# Sheet_1_2024-04-10.net
KiCad netlist of a schematic drawn in Altium Designer
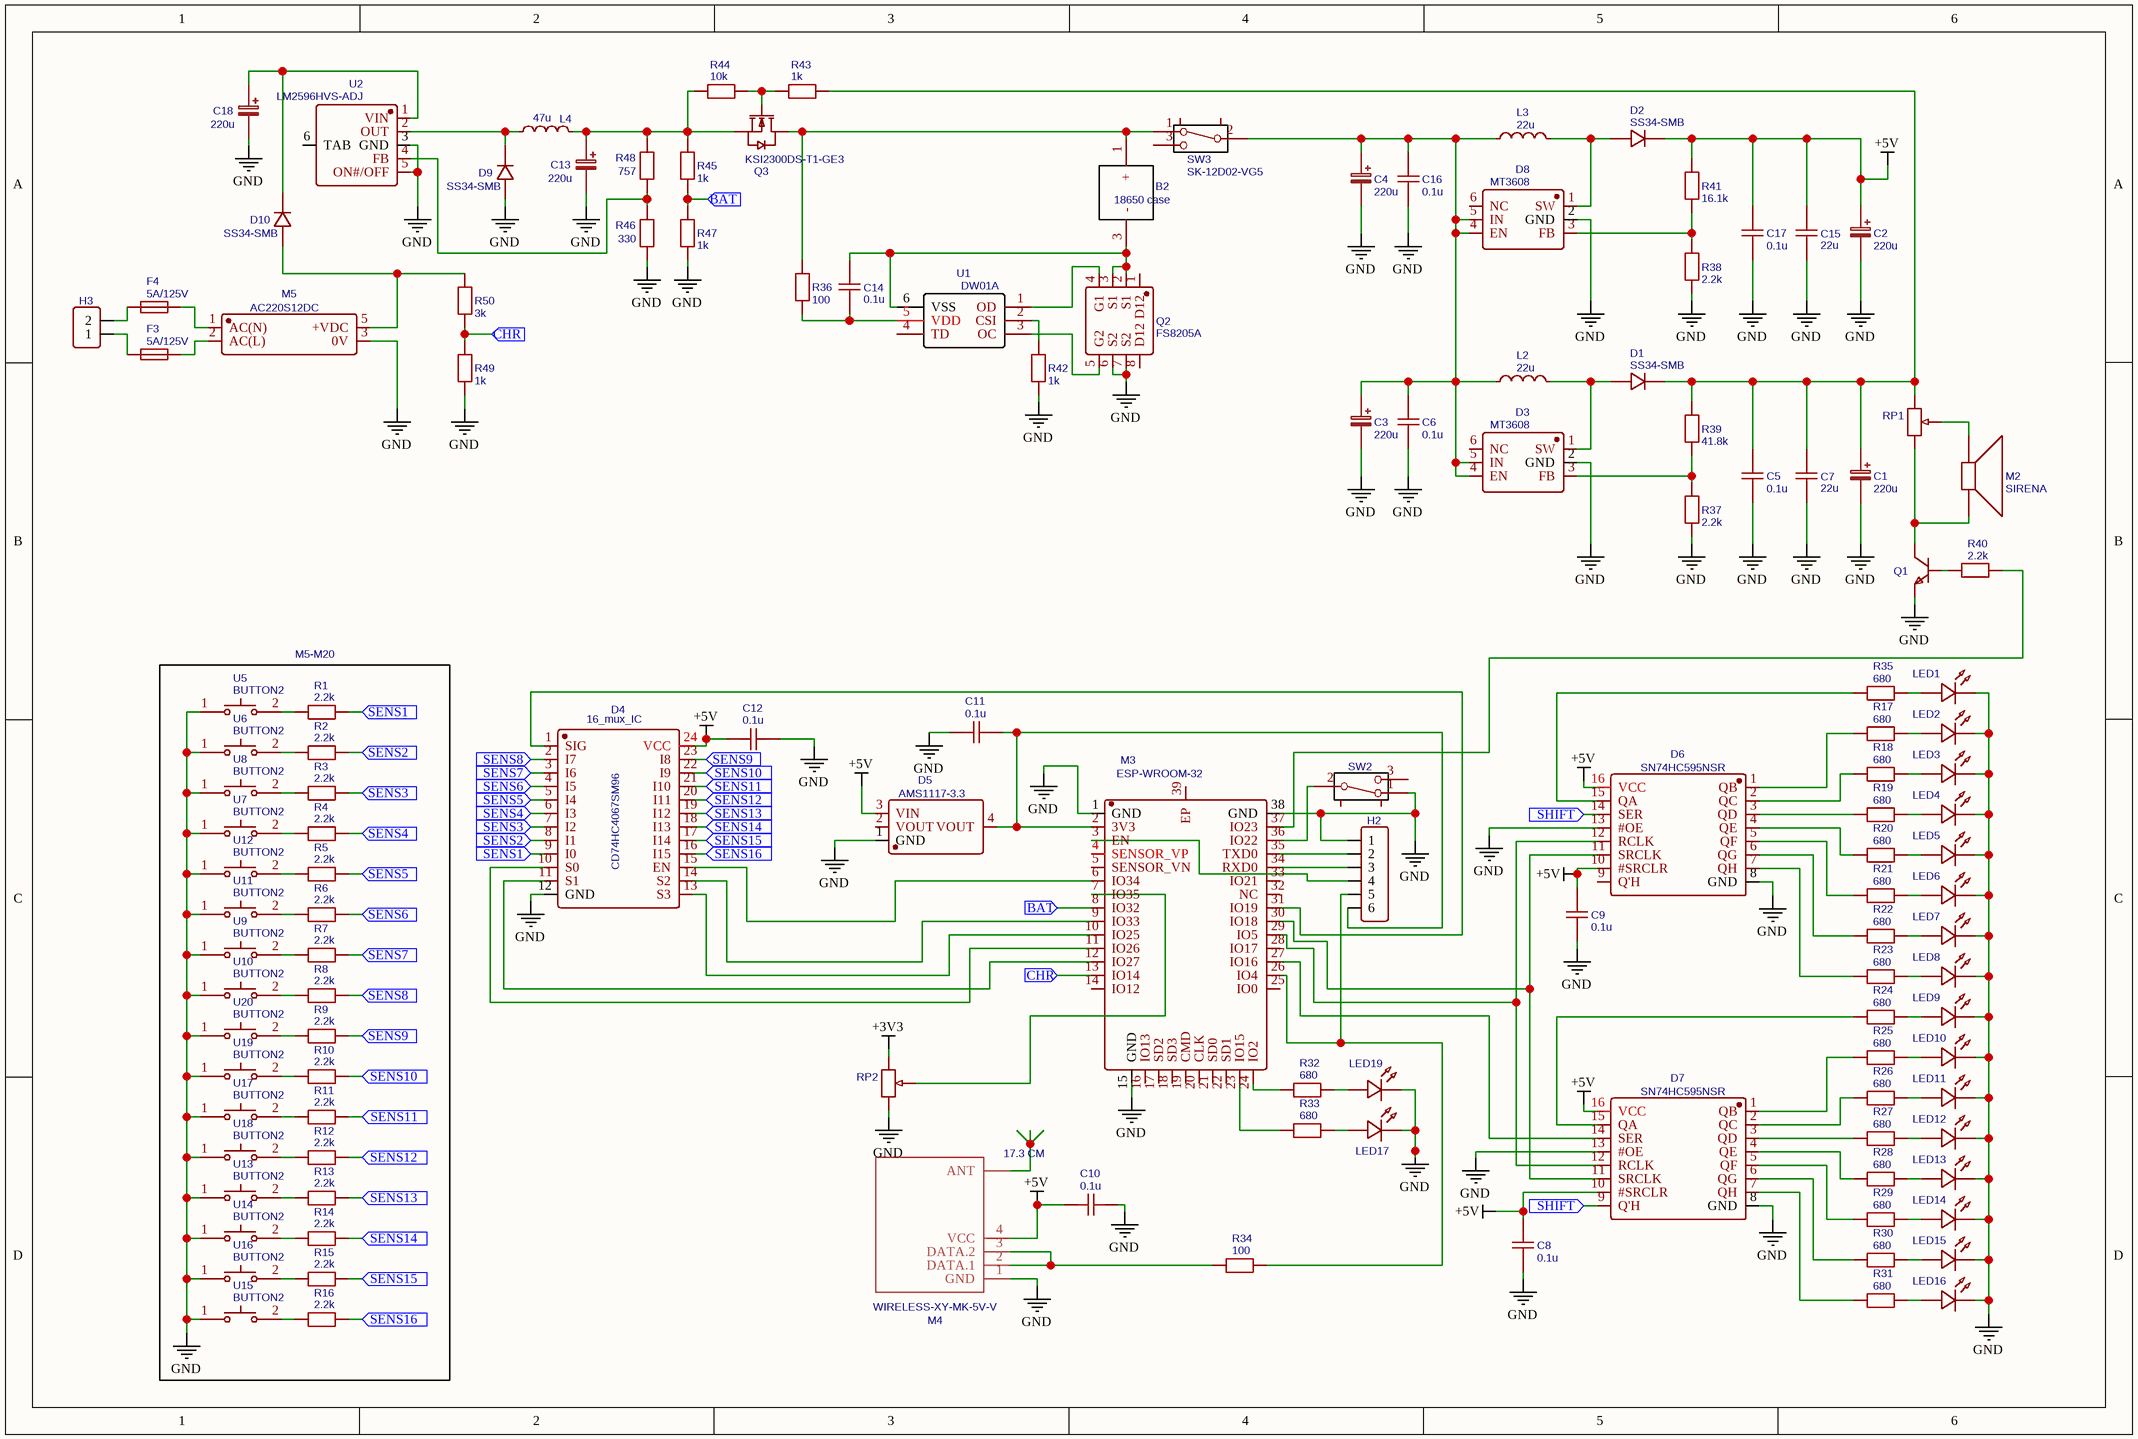
[diagram p0: Sheet_1_2024-04-10.schdoc]

(export (version "E")
  (design (tool "Eeschema 10.0.6"))
  (components
    (comp (ref "B2")
      (value "18650 case")
      (fields (field (name "CONTRIBUTOR") "s.a.timofeev93"))
      (libsource (lib "altium-import") (part "root_3_18650 case_"))
    )
    (comp (ref "C1")
      (value "220u")
      (fields (field (name "CONTRIBUTOR") "LCEDA_Lib"))
      (libsource (lib "altium-import") (part "root_3_220u_"))
    )
    (comp (ref "C2")
      (value "220u")
      (fields (field (name "CONTRIBUTOR") "LCEDA_Lib"))
      (libsource (lib "altium-import") (part "root_3_220u_"))
    )
    (comp (ref "C3")
      (value "220u")
      (fields (field (name "CONTRIBUTOR") "LCEDA_Lib"))
      (libsource (lib "altium-import") (part "root_3_220u_"))
    )
    (comp (ref "C4")
      (value "220u")
      (fields (field (name "CONTRIBUTOR") "LCEDA_Lib"))
      (libsource (lib "altium-import") (part "root_3_220u_"))
    )
    (comp (ref "C5")
      (value "0.1u")
      (fields (field (name "CONTRIBUTOR") "LCEDA_Lib"))
      (libsource (lib "altium-import") (part "root_1_0.1u_"))
    )
    (comp (ref "C6")
      (value "0.1u")
      (fields (field (name "CONTRIBUTOR") "LCEDA_Lib"))
      (libsource (lib "altium-import") (part "root_1_0.1u_"))
    )
    (comp (ref "C7")
      (value "22u")
      (fields (field (name "CONTRIBUTOR") "LCEDA_Lib"))
      (libsource (lib "altium-import") (part "root_3_22u_"))
    )
    (comp (ref "C8")
      (value "0.1u")
      (fields (field (name "CONTRIBUTOR") "LCEDA_Lib"))
      (libsource (lib "altium-import") (part "root_1_0.1u_"))
    )
    (comp (ref "C9")
      (value "0.1u")
      (fields (field (name "CONTRIBUTOR") "LCEDA_Lib"))
      (libsource (lib "altium-import") (part "root_1_0.1u_"))
    )
    (comp (ref "C10")
      (value "0.1u")
      (fields (field (name "CONTRIBUTOR") "LCEDA_Lib"))
      (libsource (lib "altium-import") (part "root_2_0.1u_"))
    )
    (comp (ref "C11")
      (value "0.1u")
      (fields (field (name "CONTRIBUTOR") "LCEDA_Lib"))
      (libsource (lib "altium-import") (part "root_2_0.1u_"))
    )
    (comp (ref "C12")
      (value "0.1u")
      (fields (field (name "CONTRIBUTOR") "LCEDA_Lib"))
      (libsource (lib "altium-import") (part "root_2_0.1u_"))
    )
    (comp (ref "C13")
      (value "220u")
      (fields (field (name "CONTRIBUTOR") "LCEDA_Lib"))
      (libsource (lib "altium-import") (part "root_3_220u_"))
    )
    (comp (ref "C14")
      (value "0.1u")
      (fields (field (name "CONTRIBUTOR") "LCEDA_Lib"))
      (libsource (lib "altium-import") (part "root_3_0.1u_"))
    )
    (comp (ref "C15")
      (value "22u")
      (fields (field (name "CONTRIBUTOR") "LCEDA_Lib"))
      (libsource (lib "altium-import") (part "root_3_22u_"))
    )
    (comp (ref "C16")
      (value "0.1u")
      (fields (field (name "CONTRIBUTOR") "LCEDA_Lib"))
      (libsource (lib "altium-import") (part "root_1_0.1u_"))
    )
    (comp (ref "C17")
      (value "0.1u")
      (fields (field (name "CONTRIBUTOR") "LCEDA_Lib"))
      (libsource (lib "altium-import") (part "root_1_0.1u_"))
    )
    (comp (ref "C18")
      (value "220u")
      (fields (field (name "CONTRIBUTOR") "LCEDA_Lib"))
      (libsource (lib "altium-import") (part "root_3_220u_"))
    )
    (comp (ref "D1")
      (value "SS34-SMB")
      (fields (field (name "MANUFACTURER") "GOODWORK(固得沃克)") (field (name "CONTRIBUTOR") "LCSC"))
      (libsource (lib "altium-import") (part "root_2_SS34-SMB_"))
    )
    (comp (ref "D2")
      (value "SS34-SMB")
      (fields (field (name "MANUFACTURER") "GOODWORK(固得沃克)") (field (name "CONTRIBUTOR") "LCSC"))
      (libsource (lib "altium-import") (part "root_2_SS34-SMB_"))
    )
    (comp (ref "D3")
      (value "MT3608")
      (fields (field (name "MANUFACTURER") "西安航天民芯"))
      (libsource (lib "altium-import") (part "root_0_MT3608_"))
    )
    (comp (ref "D4")
      (value "16_mux_IC")
      (fields (field (name "CONTRIBUTOR") "Jogiraju"))
      (libsource (lib "altium-import") (part "root_0_16_mux_IC_"))
    )
    (comp (ref "D5")
      (value "AMS1117-3.3")
      (fields (field (name "MANUFACTURER") "AMS"))
      (libsource (lib "altium-import") (part "root_0_AMS1117-3.3_"))
    )
    (comp (ref "D6")
      (value "SN74HC595NSR")
      (fields (field (name "MANUFACTURER") "TI(德州仪器)") (field (name "CONTRIBUTOR") "LCSC"))
      (libsource (lib "altium-import") (part "root_0_SN74HC595NSR_"))
    )
    (comp (ref "D7")
      (value "SN74HC595NSR")
      (fields (field (name "MANUFACTURER") "TI(德州仪器)") (field (name "CONTRIBUTOR") "LCSC"))
      (libsource (lib "altium-import") (part "root_0_SN74HC595NSR_"))
    )
    (comp (ref "D8")
      (value "MT3608")
      (fields (field (name "MANUFACTURER") "西安航天民芯"))
      (libsource (lib "altium-import") (part "root_0_MT3608_"))
    )
    (comp (ref "D9")
      (value "SS34-SMB")
      (fields (field (name "MANUFACTURER") "GOODWORK(固得沃克)") (field (name "CONTRIBUTOR") "LCSC"))
      (libsource (lib "altium-import") (part "root_3_SS34-SMB_"))
    )
    (comp (ref "D10")
      (value "SS34-SMB")
      (fields (field (name "MANUFACTURER") "GOODWORK(固得沃克)") (field (name "CONTRIBUTOR") "LCSC"))
      (libsource (lib "altium-import") (part "root_3_SS34-SMB_"))
    )
    (comp (ref "F3")
      (value "5A/125V")
      (fields (field (name "CONTRIBUTOR") "lcsc"))
      (libsource (lib "altium-import") (part "root_0_5A/125V_"))
    )
    (comp (ref "F4")
      (value "5A/125V")
      (fields (field (name "CONTRIBUTOR") "lcsc"))
      (libsource (lib "altium-import") (part "root_0_5A/125V_"))
    )
    (comp (ref "H2")
      (value "HDR-F-2.54_1x6")
      (fields (field (name "CONTRIBUTOR") "LCEDA_Lib"))
      (libsource (lib "altium-import") (part "root_0_HDR-F-2.54_1x6_"))
    )
    (comp (ref "H3")
      (value "HDR-F-2.54_1x2")
      (fields (field (name "CONTRIBUTOR") "LCEDA_Lib"))
      (libsource (lib "altium-import") (part "root_2_HDR-F-2.54_1x2_"))
    )
    (comp (ref "L2")
      (value "22u")
      (fields (field (name "CONTRIBUTOR") "LCEDA_Lib"))
      (libsource (lib "altium-import") (part "root_0_22u_"))
    )
    (comp (ref "L3")
      (value "22u")
      (fields (field (name "CONTRIBUTOR") "LCEDA_Lib"))
      (libsource (lib "altium-import") (part "root_0_22u_"))
    )
    (comp (ref "L4")
      (value "47u")
      (fields (field (name "CONTRIBUTOR") "LCEDA_Lib"))
      (libsource (lib "altium-import") (part "root_0_47u_"))
    )
    (comp (ref "LED1")
      (value "LED-TH-5mm_R")
      (fields
        (field (name "MANUFACTURER") "EVERLIGHT(台湾亿光)")
        (field (name "MANUFACTURER PART") "333-2SURD/S530-A3")
        (field (name "CONTRIBUTOR") "LCEDA_Lib")
      )
      (libsource (lib "altium-import") (part "root_0_LED-TH-5mm_R_"))
    )
    (comp (ref "LED2")
      (value "LED-TH-5mm_R")
      (fields
        (field (name "MANUFACTURER") "EVERLIGHT(台湾亿光)")
        (field (name "MANUFACTURER PART") "333-2SURD/S530-A3")
        (field (name "CONTRIBUTOR") "LCEDA_Lib")
      )
      (libsource (lib "altium-import") (part "root_0_LED-TH-5mm_R_"))
    )
    (comp (ref "LED3")
      (value "LED-TH-5mm_R")
      (fields
        (field (name "MANUFACTURER") "EVERLIGHT(台湾亿光)")
        (field (name "MANUFACTURER PART") "333-2SURD/S530-A3")
        (field (name "CONTRIBUTOR") "LCEDA_Lib")
      )
      (libsource (lib "altium-import") (part "root_0_LED-TH-5mm_R_"))
    )
    (comp (ref "LED4")
      (value "LED-TH-5mm_R")
      (fields
        (field (name "MANUFACTURER") "EVERLIGHT(台湾亿光)")
        (field (name "MANUFACTURER PART") "333-2SURD/S530-A3")
        (field (name "CONTRIBUTOR") "LCEDA_Lib")
      )
      (libsource (lib "altium-import") (part "root_0_LED-TH-5mm_R_"))
    )
    (comp (ref "LED5")
      (value "LED-TH-5mm_R")
      (fields
        (field (name "MANUFACTURER") "EVERLIGHT(台湾亿光)")
        (field (name "MANUFACTURER PART") "333-2SURD/S530-A3")
        (field (name "CONTRIBUTOR") "LCEDA_Lib")
      )
      (libsource (lib "altium-import") (part "root_0_LED-TH-5mm_R_"))
    )
    (comp (ref "LED6")
      (value "LED-TH-5mm_R")
      (fields
        (field (name "MANUFACTURER") "EVERLIGHT(台湾亿光)")
        (field (name "MANUFACTURER PART") "333-2SURD/S530-A3")
        (field (name "CONTRIBUTOR") "LCEDA_Lib")
      )
      (libsource (lib "altium-import") (part "root_0_LED-TH-5mm_R_"))
    )
    (comp (ref "LED7")
      (value "LED-TH-5mm_R")
      (fields
        (field (name "MANUFACTURER") "EVERLIGHT(台湾亿光)")
        (field (name "MANUFACTURER PART") "333-2SURD/S530-A3")
        (field (name "CONTRIBUTOR") "LCEDA_Lib")
      )
      (libsource (lib "altium-import") (part "root_0_LED-TH-5mm_R_"))
    )
    (comp (ref "LED8")
      (value "LED-TH-5mm_R")
      (fields
        (field (name "MANUFACTURER") "EVERLIGHT(台湾亿光)")
        (field (name "MANUFACTURER PART") "333-2SURD/S530-A3")
        (field (name "CONTRIBUTOR") "LCEDA_Lib")
      )
      (libsource (lib "altium-import") (part "root_0_LED-TH-5mm_R_"))
    )
    (comp (ref "LED9")
      (value "LED-TH-5mm_R")
      (fields
        (field (name "MANUFACTURER") "EVERLIGHT(台湾亿光)")
        (field (name "MANUFACTURER PART") "333-2SURD/S530-A3")
        (field (name "CONTRIBUTOR") "LCEDA_Lib")
      )
      (libsource (lib "altium-import") (part "root_0_LED-TH-5mm_R_"))
    )
    (comp (ref "LED10")
      (value "LED-TH-5mm_R")
      (fields
        (field (name "MANUFACTURER") "EVERLIGHT(台湾亿光)")
        (field (name "MANUFACTURER PART") "333-2SURD/S530-A3")
        (field (name "CONTRIBUTOR") "LCEDA_Lib")
      )
      (libsource (lib "altium-import") (part "root_0_LED-TH-5mm_R_"))
    )
    (comp (ref "LED11")
      (value "LED-TH-5mm_R")
      (fields
        (field (name "MANUFACTURER") "EVERLIGHT(台湾亿光)")
        (field (name "MANUFACTURER PART") "333-2SURD/S530-A3")
        (field (name "CONTRIBUTOR") "LCEDA_Lib")
      )
      (libsource (lib "altium-import") (part "root_0_LED-TH-5mm_R_"))
    )
    (comp (ref "LED12")
      (value "LED-TH-5mm_R")
      (fields
        (field (name "MANUFACTURER") "EVERLIGHT(台湾亿光)")
        (field (name "MANUFACTURER PART") "333-2SURD/S530-A3")
        (field (name "CONTRIBUTOR") "LCEDA_Lib")
      )
      (libsource (lib "altium-import") (part "root_0_LED-TH-5mm_R_"))
    )
    (comp (ref "LED13")
      (value "LED-TH-5mm_R")
      (fields
        (field (name "MANUFACTURER") "EVERLIGHT(台湾亿光)")
        (field (name "MANUFACTURER PART") "333-2SURD/S530-A3")
        (field (name "CONTRIBUTOR") "LCEDA_Lib")
      )
      (libsource (lib "altium-import") (part "root_0_LED-TH-5mm_R_"))
    )
    (comp (ref "LED14")
      (value "LED-TH-5mm_R")
      (fields
        (field (name "MANUFACTURER") "EVERLIGHT(台湾亿光)")
        (field (name "MANUFACTURER PART") "333-2SURD/S530-A3")
        (field (name "CONTRIBUTOR") "LCEDA_Lib")
      )
      (libsource (lib "altium-import") (part "root_0_LED-TH-5mm_R_"))
    )
    (comp (ref "LED15")
      (value "LED-TH-5mm_R")
      (fields
        (field (name "MANUFACTURER") "EVERLIGHT(台湾亿光)")
        (field (name "MANUFACTURER PART") "333-2SURD/S530-A3")
        (field (name "CONTRIBUTOR") "LCEDA_Lib")
      )
      (libsource (lib "altium-import") (part "root_0_LED-TH-5mm_R_"))
    )
    (comp (ref "LED16")
      (value "LED-TH-5mm_R")
      (fields
        (field (name "MANUFACTURER") "EVERLIGHT(台湾亿光)")
        (field (name "MANUFACTURER PART") "333-2SURD/S530-A3")
        (field (name "CONTRIBUTOR") "LCEDA_Lib")
      )
      (libsource (lib "altium-import") (part "root_0_LED-TH-5mm_R_"))
    )
    (comp (ref "LED17")
      (value "LED-TH-5mm_G")
      (fields
        (field (name "MANUFACTURER") "EVERLIGHT(台湾亿光)")
        (field (name "MANUFACTURER PART") "333-2SYGD/S530-E2")
        (field (name "CONTRIBUTOR") "LCEDA_Lib")
      )
      (libsource (lib "altium-import") (part "root_0_LED-TH-5mm_G_"))
    )
    (comp (ref "LED19")
      (value "LED-TH-5mm_B")
      (fields (field (name "CONTRIBUTOR") "LCEDA_Lib"))
      (libsource (lib "altium-import") (part "root_0_LED-TH-5mm_B_"))
    )
    (comp (ref "M2")
      (value "SIRENA")
      (fields (field (name "CONTRIBUTOR") "albertocruz"))
      (libsource (lib "altium-import") (part "root_0_SIRENA_"))
    )
    (comp (ref "M3")
      (value "ESP-WROOM-32")
      (fields
        (field (name "MANUFACTURER") "ESPRESSIF(乐鑫)")
        (field (name "MANUFACTURER PART") "ESP32-WROOM-32")
      )
      (libsource (lib "altium-import") (part "root_0_ESP-WROOM-32_"))
    )
    (comp (ref "M4")
      (value "WIRELESS-XY-MK-5V-V")
      (fields (field (name "CONTRIBUTOR") "Krzysztof"))
      (libsource (lib "altium-import") (part "root_0_WIRELESS-XY-MK-5V-V_"))
    )
    (comp (ref "M5")
      (value "AC220S12DC")
      (fields
        (field (name "MANUFACTURER") "HenLv(恒率)")
        (field (name "MANUFACTURER PART") "AC220S12DC-3W")
        (field (name "CONTRIBUTOR") "LCSC")
      )
      (libsource (lib "altium-import") (part "root_0_AC220S12DC_"))
    )
    (comp (ref "Q1")
      (value "2N3904(SOT-23)")
      (fields
        (field (name "MANUFACTURER") "KEC")
        (field (name "MANUFACTURER PART") "2n3904S-RTK/PS")
        (field (name "CONTRIBUTOR") "LCEDA_Lib")
      )
      (libsource (lib "altium-import") (part "root_0_2N3904(SOT-23)_"))
    )
    (comp (ref "Q2")
      (value "FS8205A")
      (fields (field (name "MANUFACTURER") "FORTUNE(富晶)"))
      (libsource (lib "altium-import") (part "root_3_FS8205A_"))
    )
    (comp (ref "Q3")
      (value "KSI2300DS-T1-GE3")
      (fields (field (name "MANUFACTURER") "KUU") (field (name "CONTRIBUTOR") "LCSC"))
      (libsource (lib "altium-import") (part "root_1_KSI2300DS-T1-GE3_"))
    )
    (comp (ref "R1")
      (value "2.2k")
      (fields (field (name "CONTRIBUTOR") "LCEDA_Lib"))
      (libsource (lib "altium-import") (part "root_0_2.2k_"))
    )
    (comp (ref "R2")
      (value "2.2k")
      (fields (field (name "CONTRIBUTOR") "LCEDA_Lib"))
      (libsource (lib "altium-import") (part "root_0_2.2k_"))
    )
    (comp (ref "R3")
      (value "2.2k")
      (fields (field (name "CONTRIBUTOR") "LCEDA_Lib"))
      (libsource (lib "altium-import") (part "root_0_2.2k_"))
    )
    (comp (ref "R4")
      (value "2.2k")
      (fields (field (name "CONTRIBUTOR") "LCEDA_Lib"))
      (libsource (lib "altium-import") (part "root_0_2.2k_"))
    )
    (comp (ref "R5")
      (value "2.2k")
      (fields (field (name "CONTRIBUTOR") "LCEDA_Lib"))
      (libsource (lib "altium-import") (part "root_0_2.2k_"))
    )
    (comp (ref "R6")
      (value "2.2k")
      (fields (field (name "CONTRIBUTOR") "LCEDA_Lib"))
      (libsource (lib "altium-import") (part "root_0_2.2k_"))
    )
    (comp (ref "R7")
      (value "2.2k")
      (fields (field (name "CONTRIBUTOR") "LCEDA_Lib"))
      (libsource (lib "altium-import") (part "root_0_2.2k_"))
    )
    (comp (ref "R8")
      (value "2.2k")
      (fields (field (name "CONTRIBUTOR") "LCEDA_Lib"))
      (libsource (lib "altium-import") (part "root_0_2.2k_"))
    )
    (comp (ref "R9")
      (value "2.2k")
      (fields (field (name "CONTRIBUTOR") "LCEDA_Lib"))
      (libsource (lib "altium-import") (part "root_0_2.2k_"))
    )
    (comp (ref "R10")
      (value "2.2k")
      (fields (field (name "CONTRIBUTOR") "LCEDA_Lib"))
      (libsource (lib "altium-import") (part "root_0_2.2k_"))
    )
    (comp (ref "R11")
      (value "2.2k")
      (fields (field (name "CONTRIBUTOR") "LCEDA_Lib"))
      (libsource (lib "altium-import") (part "root_0_2.2k_"))
    )
    (comp (ref "R12")
      (value "2.2k")
      (fields (field (name "CONTRIBUTOR") "LCEDA_Lib"))
      (libsource (lib "altium-import") (part "root_0_2.2k_"))
    )
    (comp (ref "R13")
      (value "2.2k")
      (fields (field (name "CONTRIBUTOR") "LCEDA_Lib"))
      (libsource (lib "altium-import") (part "root_0_2.2k_"))
    )
    (comp (ref "R14")
      (value "2.2k")
      (fields (field (name "CONTRIBUTOR") "LCEDA_Lib"))
      (libsource (lib "altium-import") (part "root_0_2.2k_"))
    )
    (comp (ref "R15")
      (value "2.2k")
      (fields (field (name "CONTRIBUTOR") "LCEDA_Lib"))
      (libsource (lib "altium-import") (part "root_0_2.2k_"))
    )
    (comp (ref "R16")
      (value "2.2k")
      (fields (field (name "CONTRIBUTOR") "LCEDA_Lib"))
      (libsource (lib "altium-import") (part "root_0_2.2k_"))
    )
    (comp (ref "R17")
      (value "680")
      (fields (field (name "CONTRIBUTOR") "LCEDA_Lib"))
      (libsource (lib "altium-import") (part "root_0_680_"))
    )
    (comp (ref "R18")
      (value "680")
      (fields (field (name "CONTRIBUTOR") "LCEDA_Lib"))
      (libsource (lib "altium-import") (part "root_0_680_"))
    )
    (comp (ref "R19")
      (value "680")
      (fields (field (name "CONTRIBUTOR") "LCEDA_Lib"))
      (libsource (lib "altium-import") (part "root_0_680_"))
    )
    (comp (ref "R20")
      (value "680")
      (fields (field (name "CONTRIBUTOR") "LCEDA_Lib"))
      (libsource (lib "altium-import") (part "root_0_680_"))
    )
    (comp (ref "R21")
      (value "680")
      (fields (field (name "CONTRIBUTOR") "LCEDA_Lib"))
      (libsource (lib "altium-import") (part "root_0_680_"))
    )
    (comp (ref "R22")
      (value "680")
      (fields (field (name "CONTRIBUTOR") "LCEDA_Lib"))
      (libsource (lib "altium-import") (part "root_0_680_"))
    )
    (comp (ref "R23")
      (value "680")
      (fields (field (name "CONTRIBUTOR") "LCEDA_Lib"))
      (libsource (lib "altium-import") (part "root_0_680_"))
    )
    (comp (ref "R24")
      (value "680")
      (fields (field (name "CONTRIBUTOR") "LCEDA_Lib"))
      (libsource (lib "altium-import") (part "root_0_680_"))
    )
    (comp (ref "R25")
      (value "680")
      (fields (field (name "CONTRIBUTOR") "LCEDA_Lib"))
      (libsource (lib "altium-import") (part "root_0_680_"))
    )
    (comp (ref "R26")
      (value "680")
      (fields (field (name "CONTRIBUTOR") "LCEDA_Lib"))
      (libsource (lib "altium-import") (part "root_0_680_"))
    )
    (comp (ref "R27")
      (value "680")
      (fields (field (name "CONTRIBUTOR") "LCEDA_Lib"))
      (libsource (lib "altium-import") (part "root_0_680_"))
    )
    (comp (ref "R28")
      (value "680")
      (fields (field (name "CONTRIBUTOR") "LCEDA_Lib"))
      (libsource (lib "altium-import") (part "root_0_680_"))
    )
    (comp (ref "R29")
      (value "680")
      (fields (field (name "CONTRIBUTOR") "LCEDA_Lib"))
      (libsource (lib "altium-import") (part "root_0_680_"))
    )
    (comp (ref "R30")
      (value "680")
      (fields (field (name "CONTRIBUTOR") "LCEDA_Lib"))
      (libsource (lib "altium-import") (part "root_0_680_"))
    )
    (comp (ref "R31")
      (value "680")
      (fields (field (name "CONTRIBUTOR") "LCEDA_Lib"))
      (libsource (lib "altium-import") (part "root_0_680_"))
    )
    (comp (ref "R32")
      (value "680")
      (fields (field (name "CONTRIBUTOR") "LCEDA_Lib"))
      (libsource (lib "altium-import") (part "root_0_680_"))
    )
    (comp (ref "R33")
      (value "680")
      (fields (field (name "CONTRIBUTOR") "LCEDA_Lib"))
      (libsource (lib "altium-import") (part "root_0_680_"))
    )
    (comp (ref "R34")
      (value "100")
      (fields (field (name "CONTRIBUTOR") "LCEDA_Lib"))
      (libsource (lib "altium-import") (part "root_0_100_"))
    )
    (comp (ref "R35")
      (value "680")
      (fields (field (name "CONTRIBUTOR") "LCEDA_Lib"))
      (libsource (lib "altium-import") (part "root_0_680_"))
    )
    (comp (ref "R36")
      (value "100")
      (fields (field (name "CONTRIBUTOR") "LCEDA_Lib"))
      (libsource (lib "altium-import") (part "root_1_100_"))
    )
    (comp (ref "R37")
      (value "2.2k")
      (fields (field (name "CONTRIBUTOR") "LCEDA_Lib"))
      (libsource (lib "altium-import") (part "root_1_2.2k_"))
    )
    (comp (ref "R38")
      (value "2.2k")
      (fields (field (name "CONTRIBUTOR") "LCEDA_Lib"))
      (libsource (lib "altium-import") (part "root_1_2.2k_"))
    )
    (comp (ref "R39")
      (value "41.8k")
      (fields (field (name "CONTRIBUTOR") "LCEDA_Lib"))
      (libsource (lib "altium-import") (part "root_1_41.8k_"))
    )
    (comp (ref "R40")
      (value "2.2k")
      (fields (field (name "CONTRIBUTOR") "LCEDA_Lib"))
      (libsource (lib "altium-import") (part "root_0_2.2k_"))
    )
    (comp (ref "R41")
      (value "16.1k")
      (fields (field (name "CONTRIBUTOR") "LCEDA_Lib"))
      (libsource (lib "altium-import") (part "root_1_16.1k_"))
    )
    (comp (ref "R42")
      (value "1k")
      (fields (field (name "CONTRIBUTOR") "LCEDA_Lib"))
      (libsource (lib "altium-import") (part "root_1_1k_"))
    )
    (comp (ref "R43")
      (value "1k")
      (fields (field (name "CONTRIBUTOR") "LCEDA_Lib"))
      (libsource (lib "altium-import") (part "root_2_1k_"))
    )
    (comp (ref "R44")
      (value "10k")
      (fields (field (name "CONTRIBUTOR") "LCEDA_Lib"))
      (libsource (lib "altium-import") (part "root_2_10k_"))
    )
    (comp (ref "R45")
      (value "1k")
      (fields (field (name "CONTRIBUTOR") "LCEDA_Lib"))
      (libsource (lib "altium-import") (part "root_3_1k_"))
    )
    (comp (ref "R46")
      (value "330")
      (fields (field (name "CONTRIBUTOR") "LCEDA_Lib"))
      (libsource (lib "altium-import") (part "root_3_330_"))
    )
    (comp (ref "R47")
      (value "1k")
      (fields (field (name "CONTRIBUTOR") "LCEDA_Lib"))
      (libsource (lib "altium-import") (part "root_3_1k_"))
    )
    (comp (ref "R48")
      (value "757")
      (fields (field (name "CONTRIBUTOR") "LCEDA_Lib"))
      (libsource (lib "altium-import") (part "root_3_757_"))
    )
    (comp (ref "R49")
      (value "1k")
      (fields (field (name "CONTRIBUTOR") "LCEDA_Lib"))
      (libsource (lib "altium-import") (part "root_3_1k_"))
    )
    (comp (ref "R50")
      (value "3k")
      (fields (field (name "CONTRIBUTOR") "LCEDA_Lib"))
      (libsource (lib "altium-import") (part "root_3_3k_"))
    )
    (comp (ref "RP1")
      (value "R_3386P_EU")
      (fields (field (name "CONTRIBUTOR") "LCEDA_Lib"))
      (libsource (lib "altium-import") (part "root_3_R_3386P_EU_"))
    )
    (comp (ref "RP2")
      (value "R_3386P_EU")
      (fields (field (name "CONTRIBUTOR") "LCEDA_Lib"))
      (libsource (lib "altium-import") (part "root_3_R_3386P_EU_"))
    )
    (comp (ref "SW2")
      (value "SK-12D02-VG5")
      (fields
        (field (name "MANUFACTURER") "Rectangular Connectors - Contacts")
        (field (name "CONTRIBUTOR") "LCSC")
      )
      (libsource (lib "altium-import") (part "root_0_SK-12D02-VG5_"))
    )
    (comp (ref "SW3")
      (value "SK-12D02-VG5")
      (fields
        (field (name "MANUFACTURER") "Rectangular Connectors - Contacts")
        (field (name "CONTRIBUTOR") "LCSC")
      )
      (libsource (lib "altium-import") (part "root_2_SK-12D02-VG5_"))
    )
    (comp (ref "U1") (value "DW01A") (libsource (lib "altium-import") (part "root_2_DW01A_")))
    (comp (ref "U2")
      (value "LM2596HVS-ADJ")
      (fields (field (name "MANUFACTURER") "UMW(友台半导体)") (field (name "CONTRIBUTOR") "LCSC"))
      (libsource (lib "altium-import") (part "root_0_LM2596HVS-ADJ_"))
    )
    (comp (ref "U5")
      (value "BUTTON2")
      (fields (field (name "CONTRIBUTOR") "LCSC"))
      (libsource (lib "altium-import") (part "root_0_BUTTON2_"))
    )
    (comp (ref "U6")
      (value "BUTTON2")
      (fields (field (name "CONTRIBUTOR") "LCSC"))
      (libsource (lib "altium-import") (part "root_0_BUTTON2_"))
    )
    (comp (ref "U7")
      (value "BUTTON2")
      (fields (field (name "CONTRIBUTOR") "LCSC"))
      (libsource (lib "altium-import") (part "root_0_BUTTON2_"))
    )
    (comp (ref "U8")
      (value "BUTTON2")
      (fields (field (name "CONTRIBUTOR") "LCSC"))
      (libsource (lib "altium-import") (part "root_0_BUTTON2_"))
    )
    (comp (ref "U9")
      (value "BUTTON2")
      (fields (field (name "CONTRIBUTOR") "LCSC"))
      (libsource (lib "altium-import") (part "root_0_BUTTON2_"))
    )
    (comp (ref "U10")
      (value "BUTTON2")
      (fields (field (name "CONTRIBUTOR") "LCSC"))
      (libsource (lib "altium-import") (part "root_0_BUTTON2_"))
    )
    (comp (ref "U11")
      (value "BUTTON2")
      (fields (field (name "CONTRIBUTOR") "LCSC"))
      (libsource (lib "altium-import") (part "root_0_BUTTON2_"))
    )
    (comp (ref "U12")
      (value "BUTTON2")
      (fields (field (name "CONTRIBUTOR") "LCSC"))
      (libsource (lib "altium-import") (part "root_0_BUTTON2_"))
    )
    (comp (ref "U13")
      (value "BUTTON2")
      (fields (field (name "CONTRIBUTOR") "LCSC"))
      (libsource (lib "altium-import") (part "root_0_BUTTON2_"))
    )
    (comp (ref "U14")
      (value "BUTTON2")
      (fields (field (name "CONTRIBUTOR") "LCSC"))
      (libsource (lib "altium-import") (part "root_0_BUTTON2_"))
    )
    (comp (ref "U15")
      (value "BUTTON2")
      (fields (field (name "CONTRIBUTOR") "LCSC"))
      (libsource (lib "altium-import") (part "root_0_BUTTON2_"))
    )
    (comp (ref "U16")
      (value "BUTTON2")
      (fields (field (name "CONTRIBUTOR") "LCSC"))
      (libsource (lib "altium-import") (part "root_0_BUTTON2_"))
    )
    (comp (ref "U17")
      (value "BUTTON2")
      (fields (field (name "CONTRIBUTOR") "LCSC"))
      (libsource (lib "altium-import") (part "root_0_BUTTON2_"))
    )
    (comp (ref "U18")
      (value "BUTTON2")
      (fields (field (name "CONTRIBUTOR") "LCSC"))
      (libsource (lib "altium-import") (part "root_0_BUTTON2_"))
    )
    (comp (ref "U19")
      (value "BUTTON2")
      (fields (field (name "CONTRIBUTOR") "LCSC"))
      (libsource (lib "altium-import") (part "root_0_BUTTON2_"))
    )
    (comp (ref "U20")
      (value "BUTTON2")
      (fields (field (name "CONTRIBUTOR") "LCSC"))
      (libsource (lib "altium-import") (part "root_0_BUTTON2_"))
    )
  )
  (nets
    (net (code "1") (name "+3V3") (class "Default")
      (node (ref "RP2") (pin "1") (pinfunction "1_1") (pintype "passive"))
    )
    (net (code "2") (name "+5V") (class "Default")
      (node (ref "C10") (pin "2") (pinfunction "2_2") (pintype "passive"))
      (node (ref "C12") (pin "2") (pinfunction "2_2") (pintype "passive"))
      (node (ref "C15") (pin "1") (pinfunction "1_1") (pintype "passive"))
      (node (ref "C17") (pin "2") (pinfunction "2_2") (pintype "passive"))
      (node (ref "C2") (pin "1") (pinfunction "1_1") (pintype "passive"))
      (node (ref "C8") (pin "2") (pinfunction "2_2") (pintype "passive"))
      (node (ref "C9") (pin "2") (pinfunction "2_2") (pintype "passive"))
      (node (ref "D2") (pin "1") (pinfunction "C_1") (pintype "passive"))
      (node (ref "D4") (pin "24") (pinfunction "VCC_24") (pintype "passive"))
      (node (ref "D5") (pin "3") (pinfunction "VIN_3") (pintype "passive"))
      (node (ref "D6") (pin "10") (pinfunction "#SRCLR_10") (pintype "passive"))
      (node (ref "D6") (pin "16") (pinfunction "VCC_16") (pintype "passive"))
      (node (ref "D7") (pin "10") (pinfunction "#SRCLR_10") (pintype "passive"))
      (node (ref "D7") (pin "16") (pinfunction "VCC_16") (pintype "passive"))
      (node (ref "M4") (pin "4") (pinfunction "VCC_4") (pintype "passive"))
      (node (ref "R41") (pin "2") (pinfunction "2_2") (pintype "passive"))
    )
    (net (code "3") (name "/BAT") (class "Default")
      (node (ref "M3") (pin "8") (pinfunction "IO32_8") (pintype "passive"))
      (node (ref "R45") (pin "2") (pinfunction "2_2") (pintype "passive"))
      (node (ref "R47") (pin "1") (pinfunction "1_1") (pintype "passive"))
    )
    (net (code "4") (name "/CHR") (class "Default")
      (node (ref "M3") (pin "13") (pinfunction "IO14_13") (pintype "passive"))
      (node (ref "R49") (pin "1") (pinfunction "1_1") (pintype "passive"))
      (node (ref "R50") (pin "2") (pinfunction "2_2") (pintype "passive"))
    )
    (net (code "5") (name "/SENS1") (class "Default")
      (node (ref "D4") (pin "9") (pinfunction "I0_9") (pintype "passive"))
      (node (ref "R1") (pin "2") (pinfunction "2_2") (pintype "passive"))
    )
    (net (code "6") (name "/SENS2") (class "Default")
      (node (ref "D4") (pin "8") (pinfunction "I1_8") (pintype "passive"))
      (node (ref "R2") (pin "2") (pinfunction "2_2") (pintype "passive"))
    )
    (net (code "7") (name "/SENS3") (class "Default")
      (node (ref "D4") (pin "7") (pinfunction "I2_7") (pintype "passive"))
      (node (ref "R3") (pin "2") (pinfunction "2_2") (pintype "passive"))
    )
    (net (code "8") (name "/SENS4") (class "Default")
      (node (ref "D4") (pin "6") (pinfunction "I3_6") (pintype "passive"))
      (node (ref "R4") (pin "2") (pinfunction "2_2") (pintype "passive"))
    )
    (net (code "9") (name "/SENS5") (class "Default")
      (node (ref "D4") (pin "5") (pinfunction "I4_5") (pintype "passive"))
      (node (ref "R5") (pin "2") (pinfunction "2_2") (pintype "passive"))
    )
    (net (code "10") (name "/SENS6") (class "Default")
      (node (ref "D4") (pin "4") (pinfunction "I5_4") (pintype "passive"))
      (node (ref "R6") (pin "2") (pinfunction "2_2") (pintype "passive"))
    )
    (net (code "11") (name "/SENS7") (class "Default")
      (node (ref "D4") (pin "3") (pinfunction "I6_3") (pintype "passive"))
      (node (ref "R7") (pin "2") (pinfunction "2_2") (pintype "passive"))
    )
    (net (code "12") (name "/SENS8") (class "Default")
      (node (ref "D4") (pin "2") (pinfunction "I7_2") (pintype "passive"))
      (node (ref "R8") (pin "2") (pinfunction "2_2") (pintype "passive"))
    )
    (net (code "13") (name "/SENS9") (class "Default")
      (node (ref "D4") (pin "23") (pinfunction "I8_23") (pintype "passive"))
      (node (ref "R9") (pin "2") (pinfunction "2_2") (pintype "passive"))
    )
    (net (code "14") (name "/SENS10") (class "Default")
      (node (ref "D4") (pin "22") (pinfunction "I9_22") (pintype "passive"))
      (node (ref "R10") (pin "2") (pinfunction "2_2") (pintype "passive"))
    )
    (net (code "15") (name "/SENS11") (class "Default")
      (node (ref "D4") (pin "21") (pinfunction "I10_21") (pintype "passive"))
      (node (ref "R11") (pin "2") (pinfunction "2_2") (pintype "passive"))
    )
    (net (code "16") (name "/SENS12") (class "Default")
      (node (ref "D4") (pin "20") (pinfunction "I11_20") (pintype "passive"))
      (node (ref "R12") (pin "2") (pinfunction "2_2") (pintype "passive"))
    )
    (net (code "17") (name "/SENS13") (class "Default")
      (node (ref "D4") (pin "19") (pinfunction "I12_19") (pintype "passive"))
      (node (ref "R13") (pin "2") (pinfunction "2_2") (pintype "passive"))
    )
    (net (code "18") (name "/SENS14") (class "Default")
      (node (ref "D4") (pin "18") (pinfunction "I13_18") (pintype "passive"))
      (node (ref "R14") (pin "2") (pinfunction "2_2") (pintype "passive"))
    )
    (net (code "19") (name "/SENS15") (class "Default")
      (node (ref "D4") (pin "17") (pinfunction "I14_17") (pintype "passive"))
      (node (ref "R15") (pin "2") (pinfunction "2_2") (pintype "passive"))
    )
    (net (code "20") (name "/SENS16") (class "Default")
      (node (ref "D4") (pin "16") (pinfunction "I15_16") (pintype "passive"))
      (node (ref "R16") (pin "2") (pinfunction "2_2") (pintype "passive"))
    )
    (net (code "21") (name "/SHIFT") (class "Default")
      (node (ref "D6") (pin "14") (pinfunction "SER_14") (pintype "passive"))
      (node (ref "D7") (pin "9") (pinfunction "Q'H_9") (pintype "passive"))
    )
    (net (code "22") (name "GND") (class "Default")
      (node (ref "C1") (pin "2") (pinfunction "2_2") (pintype "passive"))
      (node (ref "C10") (pin "1") (pinfunction "1_1") (pintype "passive"))
      (node (ref "C11") (pin "2") (pinfunction "2_2") (pintype "passive"))
      (node (ref "C12") (pin "1") (pinfunction "1_1") (pintype "passive"))
      (node (ref "C13") (pin "2") (pinfunction "2_2") (pintype "passive"))
      (node (ref "C15") (pin "2") (pinfunction "2_2") (pintype "passive"))
      (node (ref "C16") (pin "1") (pinfunction "1_1") (pintype "passive"))
      (node (ref "C17") (pin "1") (pinfunction "1_1") (pintype "passive"))
      (node (ref "C18") (pin "2") (pinfunction "2_2") (pintype "passive"))
      (node (ref "C2") (pin "2") (pinfunction "2_2") (pintype "passive"))
      (node (ref "C3") (pin "2") (pinfunction "2_2") (pintype "passive"))
      (node (ref "C4") (pin "2") (pinfunction "2_2") (pintype "passive"))
      (node (ref "C5") (pin "1") (pinfunction "1_1") (pintype "passive"))
      (node (ref "C6") (pin "1") (pinfunction "1_1") (pintype "passive"))
      (node (ref "C7") (pin "2") (pinfunction "2_2") (pintype "passive"))
      (node (ref "C8") (pin "1") (pinfunction "1_1") (pintype "passive"))
      (node (ref "C9") (pin "1") (pinfunction "1_1") (pintype "passive"))
      (node (ref "D3") (pin "2") (pinfunction "GND_2") (pintype "passive"))
      (node (ref "D4") (pin "12") (pinfunction "GND_12") (pintype "passive"))
      (node (ref "D5") (pin "1") (pinfunction "GND_1") (pintype "passive"))
      (node (ref "D6") (pin "13") (pinfunction "#OE_13") (pintype "passive"))
      (node (ref "D6") (pin "8") (pinfunction "GND_8") (pintype "passive"))
      (node (ref "D7") (pin "13") (pinfunction "#OE_13") (pintype "passive"))
      (node (ref "D7") (pin "8") (pinfunction "GND_8") (pintype "passive"))
      (node (ref "D8") (pin "2") (pinfunction "GND_2") (pintype "passive"))
      (node (ref "D9") (pin "2") (pinfunction "A_2") (pintype "passive"))
      (node (ref "H2") (pin "1") (pinfunction "1_1") (pintype "passive"))
      (node (ref "LED1") (pin "2") (pinfunction "2_2") (pintype "passive"))
      (node (ref "LED10") (pin "2") (pinfunction "2_2") (pintype "passive"))
      (node (ref "LED11") (pin "2") (pinfunction "2_2") (pintype "passive"))
      (node (ref "LED12") (pin "2") (pinfunction "2_2") (pintype "passive"))
      (node (ref "LED13") (pin "2") (pinfunction "2_2") (pintype "passive"))
      (node (ref "LED14") (pin "2") (pinfunction "2_2") (pintype "passive"))
      (node (ref "LED15") (pin "2") (pinfunction "2_2") (pintype "passive"))
      (node (ref "LED16") (pin "2") (pinfunction "2_2") (pintype "passive"))
      (node (ref "LED17") (pin "2") (pinfunction "2_2") (pintype "passive"))
      (node (ref "LED19") (pin "2") (pinfunction "2_2") (pintype "passive"))
      (node (ref "LED2") (pin "2") (pinfunction "2_2") (pintype "passive"))
      (node (ref "LED3") (pin "2") (pinfunction "2_2") (pintype "passive"))
      (node (ref "LED4") (pin "2") (pinfunction "2_2") (pintype "passive"))
      (node (ref "LED5") (pin "2") (pinfunction "2_2") (pintype "passive"))
      (node (ref "LED6") (pin "2") (pinfunction "2_2") (pintype "passive"))
      (node (ref "LED7") (pin "2") (pinfunction "2_2") (pintype "passive"))
      (node (ref "LED8") (pin "2") (pinfunction "2_2") (pintype "passive"))
      (node (ref "LED9") (pin "2") (pinfunction "2_2") (pintype "passive"))
      (node (ref "M3") (pin "1") (pinfunction "GND_1") (pintype "passive"))
      (node (ref "M3") (pin "15") (pinfunction "GND_15") (pintype "passive"))
      (node (ref "M3") (pin "38") (pinfunction "GND_38") (pintype "passive"))
      (node (ref "M4") (pin "1") (pinfunction "GND_1") (pintype "passive"))
      (node (ref "M5") (pin "3") (pinfunction "0V_3") (pintype "passive"))
      (node (ref "Q1") (pin "1") (pinfunction "E_1") (pintype "passive"))
      (node (ref "Q2") (pin "6") (pinfunction "S2_6") (pintype "passive"))
      (node (ref "Q2") (pin "7") (pinfunction "S2_7") (pintype "passive"))
      (node (ref "R37") (pin "1") (pinfunction "1_1") (pintype "passive"))
      (node (ref "R38") (pin "1") (pinfunction "1_1") (pintype "passive"))
      (node (ref "R42") (pin "1") (pinfunction "1_1") (pintype "passive"))
      (node (ref "R46") (pin "2") (pinfunction "2_2") (pintype "passive"))
      (node (ref "R47") (pin "2") (pinfunction "2_2") (pintype "passive"))
      (node (ref "R49") (pin "2") (pinfunction "2_2") (pintype "passive"))
      (node (ref "RP2") (pin "3") (pinfunction "3_3") (pintype "passive"))
      (node (ref "SW2") (pin "1") (pinfunction "1_1") (pintype "passive"))
      (node (ref "U10") (pin "1") (pinfunction "1_1") (pintype "passive"))
      (node (ref "U11") (pin "1") (pinfunction "1_1") (pintype "passive"))
      (node (ref "U12") (pin "1") (pinfunction "1_1") (pintype "passive"))
      (node (ref "U13") (pin "1") (pinfunction "1_1") (pintype "passive"))
      (node (ref "U14") (pin "1") (pinfunction "1_1") (pintype "passive"))
      (node (ref "U15") (pin "1") (pinfunction "1_1") (pintype "passive"))
      (node (ref "U16") (pin "1") (pinfunction "1_1") (pintype "passive"))
      (node (ref "U17") (pin "1") (pinfunction "1_1") (pintype "passive"))
      (node (ref "U18") (pin "1") (pinfunction "1_1") (pintype "passive"))
      (node (ref "U19") (pin "1") (pinfunction "1_1") (pintype "passive"))
      (node (ref "U2") (pin "3") (pinfunction "GND_3") (pintype "passive"))
      (node (ref "U2") (pin "5") (pinfunction "ON#/OFF_5") (pintype "passive"))
      (node (ref "U20") (pin "1") (pinfunction "1_1") (pintype "passive"))
      (node (ref "U5") (pin "1") (pinfunction "1_1") (pintype "passive"))
      (node (ref "U6") (pin "1") (pinfunction "1_1") (pintype "passive"))
      (node (ref "U7") (pin "1") (pinfunction "1_1") (pintype "passive"))
      (node (ref "U8") (pin "1") (pinfunction "1_1") (pintype "passive"))
      (node (ref "U9") (pin "1") (pinfunction "1_1") (pintype "passive"))
    )
    (net (code "23") (name "Net-(B2-+)") (class "Default")
      (node (ref "B2") (pin "1") (pinfunction "+_1") (pintype "passive"))
      (node (ref "Q3") (pin "3") (pinfunction "D_3") (pintype "passive"))
      (node (ref "R36") (pin "2") (pinfunction "2_2") (pintype "passive"))
      (node (ref "SW3") (pin "1") (pinfunction "1_1") (pintype "passive"))
    )
    (net (code "24") (name "Net-(B2--)") (class "Default")
      (node (ref "B2") (pin "3") (pinfunction "-_3") (pintype "passive"))
      (node (ref "C14") (pin "1") (pinfunction "1_1") (pintype "passive"))
      (node (ref "Q2") (pin "2") (pinfunction "S1_2") (pintype "passive"))
      (node (ref "Q2") (pin "3") (pinfunction "S1_3") (pintype "passive"))
      (node (ref "U1") (pin "6") (pinfunction "VSS_6") (pintype "passive"))
    )
    (net (code "25") (name "Net-(D1-A)") (class "Default")
      (node (ref "D1") (pin "2") (pinfunction "A_2") (pintype "passive"))
      (node (ref "D3") (pin "1") (pinfunction "SW_1") (pintype "passive"))
      (node (ref "L2") (pin "2") (pinfunction "2_2") (pintype "passive"))
    )
    (net (code "26") (name "Net-(D1-C)") (class "Default")
      (node (ref "C1") (pin "1") (pinfunction "1_1") (pintype "passive"))
      (node (ref "C5") (pin "2") (pinfunction "2_2") (pintype "passive"))
      (node (ref "C7") (pin "1") (pinfunction "1_1") (pintype "passive"))
      (node (ref "D1") (pin "1") (pinfunction "C_1") (pintype "passive"))
      (node (ref "R39") (pin "2") (pinfunction "2_2") (pintype "passive"))
      (node (ref "R43") (pin "1") (pinfunction "1_1") (pintype "passive"))
      (node (ref "RP1") (pin "1") (pinfunction "1_1") (pintype "passive"))
    )
    (net (code "27") (name "Net-(D2-A)") (class "Default")
      (node (ref "D2") (pin "2") (pinfunction "A_2") (pintype "passive"))
      (node (ref "D8") (pin "1") (pinfunction "SW_1") (pintype "passive"))
      (node (ref "L3") (pin "2") (pinfunction "2_2") (pintype "passive"))
    )
    (net (code "28") (name "Net-(D3-EN)") (class "Default")
      (node (ref "C16") (pin "2") (pinfunction "2_2") (pintype "passive"))
      (node (ref "C3") (pin "1") (pinfunction "1_1") (pintype "passive"))
      (node (ref "C4") (pin "1") (pinfunction "1_1") (pintype "passive"))
      (node (ref "C6") (pin "2") (pinfunction "2_2") (pintype "passive"))
      (node (ref "D3") (pin "4") (pinfunction "EN_4") (pintype "passive"))
      (node (ref "D3") (pin "5") (pinfunction "IN_5") (pintype "passive"))
      (node (ref "D8") (pin "4") (pinfunction "EN_4") (pintype "passive"))
      (node (ref "D8") (pin "5") (pinfunction "IN_5") (pintype "passive"))
      (node (ref "L2") (pin "1") (pinfunction "1_1") (pintype "passive"))
      (node (ref "L3") (pin "1") (pinfunction "1_1") (pintype "passive"))
      (node (ref "SW3") (pin "2") (pinfunction "2_2") (pintype "passive"))
    )
    (net (code "29") (name "Net-(D3-FB)") (class "Default")
      (node (ref "D3") (pin "3") (pinfunction "FB_3") (pintype "passive"))
      (node (ref "R37") (pin "2") (pinfunction "2_2") (pintype "passive"))
      (node (ref "R39") (pin "1") (pinfunction "1_1") (pintype "passive"))
    )
    (net (code "30") (name "Net-(D4-EN)") (class "Default")
      (node (ref "D4") (pin "15") (pinfunction "EN_15") (pintype "passive"))
      (node (ref "M3") (pin "6") (pinfunction "IO34_6") (pintype "passive"))
    )
    (net (code "31") (name "Net-(D4-S0)") (class "Default")
      (node (ref "D4") (pin "10") (pinfunction "S0_10") (pintype "passive"))
      (node (ref "M3") (pin "11") (pinfunction "IO26_11") (pintype "passive"))
    )
    (net (code "32") (name "Net-(D4-S1)") (class "Default")
      (node (ref "D4") (pin "11") (pinfunction "S1_11") (pintype "passive"))
      (node (ref "M3") (pin "12") (pinfunction "IO27_12") (pintype "passive"))
    )
    (net (code "33") (name "Net-(D4-S2)") (class "Default")
      (node (ref "D4") (pin "14") (pinfunction "S2_14") (pintype "passive"))
      (node (ref "M3") (pin "9") (pinfunction "IO33_9") (pintype "passive"))
    )
    (net (code "34") (name "Net-(D4-S3)") (class "Default")
      (node (ref "D4") (pin "13") (pinfunction "S3_13") (pintype "passive"))
      (node (ref "M3") (pin "10") (pinfunction "IO25_10") (pintype "passive"))
    )
    (net (code "35") (name "Net-(D4-SIG)") (class "Default")
      (node (ref "D4") (pin "1") (pinfunction "SIG_1") (pintype "passive"))
      (node (ref "M3") (pin "31") (pinfunction "IO19_31") (pintype "passive"))
    )
    (net (code "36") (name "Net-(D6-QA)") (class "Default")
      (node (ref "D6") (pin "15") (pinfunction "QA_15") (pintype "passive"))
      (node (ref "R35") (pin "1") (pinfunction "1_1") (pintype "passive"))
    )
    (net (code "37") (name "Net-(D6-QB)") (class "Default")
      (node (ref "D6") (pin "1") (pinfunction "QB_1") (pintype "passive"))
      (node (ref "R17") (pin "1") (pinfunction "1_1") (pintype "passive"))
    )
    (net (code "38") (name "Net-(D6-QC)") (class "Default")
      (node (ref "D6") (pin "2") (pinfunction "QC_2") (pintype "passive"))
      (node (ref "R18") (pin "1") (pinfunction "1_1") (pintype "passive"))
    )
    (net (code "39") (name "Net-(D6-QD)") (class "Default")
      (node (ref "D6") (pin "3") (pinfunction "QD_3") (pintype "passive"))
      (node (ref "R19") (pin "1") (pinfunction "1_1") (pintype "passive"))
    )
    (net (code "40") (name "Net-(D6-QE)") (class "Default")
      (node (ref "D6") (pin "4") (pinfunction "QE_4") (pintype "passive"))
      (node (ref "R20") (pin "1") (pinfunction "1_1") (pintype "passive"))
    )
    (net (code "41") (name "Net-(D6-QF)") (class "Default")
      (node (ref "D6") (pin "5") (pinfunction "QF_5") (pintype "passive"))
      (node (ref "R21") (pin "1") (pinfunction "1_1") (pintype "passive"))
    )
    (net (code "42") (name "Net-(D6-QG)") (class "Default")
      (node (ref "D6") (pin "6") (pinfunction "QG_6") (pintype "passive"))
      (node (ref "R22") (pin "1") (pinfunction "1_1") (pintype "passive"))
    )
    (net (code "43") (name "Net-(D6-QH)") (class "Default")
      (node (ref "D6") (pin "7") (pinfunction "QH_7") (pintype "passive"))
      (node (ref "R23") (pin "1") (pinfunction "1_1") (pintype "passive"))
    )
    (net (code "44") (name "Net-(D6-RCLK)") (class "Default")
      (node (ref "D6") (pin "12") (pinfunction "RCLK_12") (pintype "passive"))
      (node (ref "D7") (pin "12") (pinfunction "RCLK_12") (pintype "passive"))
      (node (ref "M3") (pin "29") (pinfunction "IO5_29") (pintype "passive"))
    )
    (net (code "45") (name "Net-(D6-SRCLK)") (class "Default")
      (node (ref "D6") (pin "11") (pinfunction "SRCLK_11") (pintype "passive"))
      (node (ref "D7") (pin "11") (pinfunction "SRCLK_11") (pintype "passive"))
      (node (ref "M3") (pin "30") (pinfunction "IO18_30") (pintype "passive"))
    )
    (net (code "46") (name "Net-(D7-QA)") (class "Default")
      (node (ref "D7") (pin "15") (pinfunction "QA_15") (pintype "passive"))
      (node (ref "R24") (pin "1") (pinfunction "1_1") (pintype "passive"))
    )
    (net (code "47") (name "Net-(D7-QB)") (class "Default")
      (node (ref "D7") (pin "1") (pinfunction "QB_1") (pintype "passive"))
      (node (ref "R25") (pin "1") (pinfunction "1_1") (pintype "passive"))
    )
    (net (code "48") (name "Net-(D7-QC)") (class "Default")
      (node (ref "D7") (pin "2") (pinfunction "QC_2") (pintype "passive"))
      (node (ref "R26") (pin "1") (pinfunction "1_1") (pintype "passive"))
    )
    (net (code "49") (name "Net-(D7-QD)") (class "Default")
      (node (ref "D7") (pin "3") (pinfunction "QD_3") (pintype "passive"))
      (node (ref "R27") (pin "1") (pinfunction "1_1") (pintype "passive"))
    )
    (net (code "50") (name "Net-(D7-QE)") (class "Default")
      (node (ref "D7") (pin "4") (pinfunction "QE_4") (pintype "passive"))
      (node (ref "R28") (pin "1") (pinfunction "1_1") (pintype "passive"))
    )
    (net (code "51") (name "Net-(D7-QF)") (class "Default")
      (node (ref "D7") (pin "5") (pinfunction "QF_5") (pintype "passive"))
      (node (ref "R29") (pin "1") (pinfunction "1_1") (pintype "passive"))
    )
    (net (code "52") (name "Net-(D7-QG)") (class "Default")
      (node (ref "D7") (pin "6") (pinfunction "QG_6") (pintype "passive"))
      (node (ref "R30") (pin "1") (pinfunction "1_1") (pintype "passive"))
    )
    (net (code "53") (name "Net-(D7-QH)") (class "Default")
      (node (ref "D7") (pin "7") (pinfunction "QH_7") (pintype "passive"))
      (node (ref "R31") (pin "1") (pinfunction "1_1") (pintype "passive"))
    )
    (net (code "54") (name "Net-(D7-SER)") (class "Default")
      (node (ref "D7") (pin "14") (pinfunction "SER_14") (pintype "passive"))
      (node (ref "M3") (pin "27") (pinfunction "IO16_27") (pintype "passive"))
    )
    (net (code "55") (name "Net-(D8-FB)") (class "Default")
      (node (ref "D8") (pin "3") (pinfunction "FB_3") (pintype "passive"))
      (node (ref "R38") (pin "2") (pinfunction "2_2") (pintype "passive"))
      (node (ref "R41") (pin "1") (pinfunction "1_1") (pintype "passive"))
    )
    (net (code "56") (name "Net-(D9-C)") (class "Default")
      (node (ref "D9") (pin "1") (pinfunction "C_1") (pintype "passive"))
      (node (ref "L4") (pin "2") (pinfunction "2_2") (pintype "passive"))
      (node (ref "U2") (pin "2") (pinfunction "OUT_2") (pintype "passive"))
    )
    (net (code "57") (name "Net-(D10-A)") (class "Default")
      (node (ref "D10") (pin "2") (pinfunction "A_2") (pintype "passive"))
      (node (ref "M5") (pin "5") (pinfunction "+VDC_5") (pintype "passive"))
      (node (ref "R50") (pin "1") (pinfunction "1_1") (pintype "passive"))
    )
    (net (code "58") (name "Net-(D10-C)") (class "Default")
      (node (ref "C18") (pin "1") (pinfunction "1_1") (pintype "passive"))
      (node (ref "D10") (pin "1") (pinfunction "C_1") (pintype "passive"))
      (node (ref "U2") (pin "1") (pinfunction "VIN_1") (pintype "passive"))
    )
    (net (code "59") (name "Net-(F3-Pad1)") (class "Default")
      (node (ref "F3") (pin "1") (pinfunction "1_1") (pintype "passive"))
      (node (ref "H3") (pin "1") (pinfunction "1_1") (pintype "passive"))
    )
    (net (code "60") (name "Net-(F4-Pad1)") (class "Default")
      (node (ref "F4") (pin "1") (pinfunction "1_1") (pintype "passive"))
      (node (ref "H3") (pin "2") (pinfunction "2_2") (pintype "passive"))
    )
    (net (code "61") (name "Net-(LED1-Pad1)") (class "Default")
      (node (ref "LED1") (pin "1") (pinfunction "1_1") (pintype "passive"))
      (node (ref "R35") (pin "2") (pinfunction "2_2") (pintype "passive"))
    )
    (net (code "62") (name "Net-(LED2-Pad1)") (class "Default")
      (node (ref "LED2") (pin "1") (pinfunction "1_1") (pintype "passive"))
      (node (ref "R17") (pin "2") (pinfunction "2_2") (pintype "passive"))
    )
    (net (code "63") (name "Net-(LED3-Pad1)") (class "Default")
      (node (ref "LED3") (pin "1") (pinfunction "1_1") (pintype "passive"))
      (node (ref "R18") (pin "2") (pinfunction "2_2") (pintype "passive"))
    )
    (net (code "64") (name "Net-(LED4-Pad1)") (class "Default")
      (node (ref "LED4") (pin "1") (pinfunction "1_1") (pintype "passive"))
      (node (ref "R19") (pin "2") (pinfunction "2_2") (pintype "passive"))
    )
    (net (code "65") (name "Net-(LED5-Pad1)") (class "Default")
      (node (ref "LED5") (pin "1") (pinfunction "1_1") (pintype "passive"))
      (node (ref "R20") (pin "2") (pinfunction "2_2") (pintype "passive"))
    )
    (net (code "66") (name "Net-(LED6-Pad1)") (class "Default")
      (node (ref "LED6") (pin "1") (pinfunction "1_1") (pintype "passive"))
      (node (ref "R21") (pin "2") (pinfunction "2_2") (pintype "passive"))
    )
    (net (code "67") (name "Net-(LED7-Pad1)") (class "Default")
      (node (ref "LED7") (pin "1") (pinfunction "1_1") (pintype "passive"))
      (node (ref "R22") (pin "2") (pinfunction "2_2") (pintype "passive"))
    )
    (net (code "68") (name "Net-(LED8-Pad1)") (class "Default")
      (node (ref "LED8") (pin "1") (pinfunction "1_1") (pintype "passive"))
      (node (ref "R23") (pin "2") (pinfunction "2_2") (pintype "passive"))
    )
    (net (code "69") (name "Net-(LED9-Pad1)") (class "Default")
      (node (ref "LED9") (pin "1") (pinfunction "1_1") (pintype "passive"))
      (node (ref "R24") (pin "2") (pinfunction "2_2") (pintype "passive"))
    )
    (net (code "70") (name "Net-(LED10-Pad1)") (class "Default")
      (node (ref "LED10") (pin "1") (pinfunction "1_1") (pintype "passive"))
      (node (ref "R25") (pin "2") (pinfunction "2_2") (pintype "passive"))
    )
    (net (code "71") (name "Net-(LED11-Pad1)") (class "Default")
      (node (ref "LED11") (pin "1") (pinfunction "1_1") (pintype "passive"))
      (node (ref "R26") (pin "2") (pinfunction "2_2") (pintype "passive"))
    )
    (net (code "72") (name "Net-(LED12-Pad1)") (class "Default")
      (node (ref "LED12") (pin "1") (pinfunction "1_1") (pintype "passive"))
      (node (ref "R27") (pin "2") (pinfunction "2_2") (pintype "passive"))
    )
    (net (code "73") (name "Net-(LED13-Pad1)") (class "Default")
      (node (ref "LED13") (pin "1") (pinfunction "1_1") (pintype "passive"))
      (node (ref "R28") (pin "2") (pinfunction "2_2") (pintype "passive"))
    )
    (net (code "74") (name "Net-(LED14-Pad1)") (class "Default")
      (node (ref "LED14") (pin "1") (pinfunction "1_1") (pintype "passive"))
      (node (ref "R29") (pin "2") (pinfunction "2_2") (pintype "passive"))
    )
    (net (code "75") (name "Net-(LED15-Pad1)") (class "Default")
      (node (ref "LED15") (pin "1") (pinfunction "1_1") (pintype "passive"))
      (node (ref "R30") (pin "2") (pinfunction "2_2") (pintype "passive"))
    )
    (net (code "76") (name "Net-(LED16-Pad1)") (class "Default")
      (node (ref "LED16") (pin "1") (pinfunction "1_1") (pintype "passive"))
      (node (ref "R31") (pin "2") (pinfunction "2_2") (pintype "passive"))
    )
    (net (code "77") (name "Net-(LED17-Pad1)") (class "Default")
      (node (ref "LED17") (pin "1") (pinfunction "1_1") (pintype "passive"))
      (node (ref "R33") (pin "2") (pinfunction "2_2") (pintype "passive"))
    )
    (net (code "78") (name "Net-(LED19-Pad1)") (class "Default")
      (node (ref "LED19") (pin "1") (pinfunction "1_1") (pintype "passive"))
      (node (ref "R32") (pin "2") (pinfunction "2_2") (pintype "passive"))
    )
    (net (code "79") (name "Net-(M2-Pad1)") (class "Default")
      (node (ref "M2") (pin "1") (pinfunction "1_1") (pintype "passive"))
      (node (ref "RP1") (pin "2") (pinfunction "2_2") (pintype "passive"))
    )
    (net (code "80") (name "Net-(M3-3V3)") (class "Default")
      (node (ref "C11") (pin "1") (pinfunction "1_1") (pintype "passive"))
      (node (ref "D5") (pin "4") (pinfunction "VOUT_4") (pintype "passive"))
      (node (ref "H2") (pin "6") (pinfunction "6_6") (pintype "passive"))
      (node (ref "M3") (pin "2") (pinfunction "3V3_2") (pintype "passive"))
    )
    (net (code "81") (name "Net-(M3-EN)") (class "Default")
      (node (ref "H2") (pin "4") (pinfunction "4_4") (pintype "passive"))
      (node (ref "M3") (pin "3") (pinfunction "EN_3") (pintype "passive"))
    )
    (net (code "82") (name "Net-(M3-IO2)") (class "Default")
      (node (ref "M3") (pin "24") (pinfunction "IO2_24") (pintype "passive"))
      (node (ref "R32") (pin "1") (pinfunction "1_1") (pintype "passive"))
    )
    (net (code "83") (name "Net-(M3-IO4)") (class "Default")
      (node (ref "H2") (pin "5") (pinfunction "5_5") (pintype "passive"))
      (node (ref "M3") (pin "26") (pinfunction "IO4_26") (pintype "passive"))
      (node (ref "R34") (pin "2") (pinfunction "2_2") (pintype "passive"))
    )
    (net (code "84") (name "Net-(M3-IO15)") (class "Default")
      (node (ref "M3") (pin "23") (pinfunction "IO15_23") (pintype "passive"))
      (node (ref "R33") (pin "1") (pinfunction "1_1") (pintype "passive"))
    )
    (net (code "85") (name "Net-(M3-IO22)") (class "Default")
      (node (ref "M3") (pin "36") (pinfunction "IO22_36") (pintype "passive"))
      (node (ref "SW2") (pin "2") (pinfunction "2_2") (pintype "passive"))
    )
    (net (code "86") (name "Net-(M3-IO23)") (class "Default")
      (node (ref "M3") (pin "37") (pinfunction "IO23_37") (pintype "passive"))
      (node (ref "R40") (pin "2") (pinfunction "2_2") (pintype "passive"))
    )
    (net (code "87") (name "Net-(M3-IO35)") (class "Default")
      (node (ref "M3") (pin "7") (pinfunction "IO35_7") (pintype "passive"))
      (node (ref "RP2") (pin "2") (pinfunction "2_2") (pintype "passive"))
    )
    (net (code "88") (name "Net-(M3-RXD0)") (class "Default")
      (node (ref "H2") (pin "3") (pinfunction "3_3") (pintype "passive"))
      (node (ref "M3") (pin "34") (pinfunction "RXD0_34") (pintype "passive"))
    )
    (net (code "89") (name "Net-(M3-TXD0)") (class "Default")
      (node (ref "H2") (pin "2") (pinfunction "2_2") (pintype "passive"))
      (node (ref "M3") (pin "35") (pinfunction "TXD0_35") (pintype "passive"))
    )
    (net (code "90") (name "Net-(M4-DATA.1)") (class "Default")
      (node (ref "M4") (pin "2") (pinfunction "DATA.1_2") (pintype "passive"))
      (node (ref "M4") (pin "3") (pinfunction "DATA.2_3") (pintype "passive"))
      (node (ref "R34") (pin "1") (pinfunction "1_1") (pintype "passive"))
    )
    (net (code "91") (name "Net-(M5-AC(L))") (class "Default")
      (node (ref "F3") (pin "2") (pinfunction "2_2") (pintype "passive"))
      (node (ref "M5") (pin "2") (pinfunction "AC(L)_2") (pintype "passive"))
    )
    (net (code "92") (name "Net-(M5-AC(N))") (class "Default")
      (node (ref "F4") (pin "2") (pinfunction "2_2") (pintype "passive"))
      (node (ref "M5") (pin "1") (pinfunction "AC(N)_1") (pintype "passive"))
    )
    (net (code "93") (name "Net-(Q1-B)") (class "Default")
      (node (ref "Q1") (pin "2") (pinfunction "B_2") (pintype "passive"))
      (node (ref "R40") (pin "1") (pinfunction "1_1") (pintype "passive"))
    )
    (net (code "94") (name "Net-(Q1-C)") (class "Default")
      (node (ref "M2") (pin "2") (pinfunction "2_2") (pintype "passive"))
      (node (ref "Q1") (pin "3") (pinfunction "C_3") (pintype "passive"))
      (node (ref "RP1") (pin "3") (pinfunction "3_3") (pintype "passive"))
    )
    (net (code "95") (name "Net-(Q2-G1)") (class "Default")
      (node (ref "Q2") (pin "4") (pinfunction "G1_4") (pintype "passive"))
      (node (ref "U1") (pin "1") (pinfunction "OD_1") (pintype "passive"))
    )
    (net (code "96") (name "Net-(Q2-G2)") (class "Default")
      (node (ref "Q2") (pin "5") (pinfunction "G2_5") (pintype "passive"))
      (node (ref "U1") (pin "3") (pinfunction "OC_3") (pintype "passive"))
    )
    (net (code "97") (name "Net-(Q3-G)") (class "Default")
      (node (ref "Q3") (pin "1") (pinfunction "G_1") (pintype "passive"))
      (node (ref "R43") (pin "2") (pinfunction "2_2") (pintype "passive"))
      (node (ref "R44") (pin "1") (pinfunction "1_1") (pintype "passive"))
    )
    (net (code "98") (name "Net-(Q3-S)") (class "Default")
      (node (ref "C13") (pin "1") (pinfunction "1_1") (pintype "passive"))
      (node (ref "L4") (pin "1") (pinfunction "1_1") (pintype "passive"))
      (node (ref "Q3") (pin "2") (pinfunction "S_2") (pintype "passive"))
      (node (ref "R44") (pin "2") (pinfunction "2_2") (pintype "passive"))
      (node (ref "R45") (pin "1") (pinfunction "1_1") (pintype "passive"))
      (node (ref "R48") (pin "1") (pinfunction "1_1") (pintype "passive"))
    )
    (net (code "99") (name "Net-(R1-Pad1)") (class "Default")
      (node (ref "R1") (pin "1") (pinfunction "1_1") (pintype "passive"))
      (node (ref "U5") (pin "2") (pinfunction "2_2") (pintype "passive"))
    )
    (net (code "100") (name "Net-(R2-Pad1)") (class "Default")
      (node (ref "R2") (pin "1") (pinfunction "1_1") (pintype "passive"))
      (node (ref "U6") (pin "2") (pinfunction "2_2") (pintype "passive"))
    )
    (net (code "101") (name "Net-(R3-Pad1)") (class "Default")
      (node (ref "R3") (pin "1") (pinfunction "1_1") (pintype "passive"))
      (node (ref "U8") (pin "2") (pinfunction "2_2") (pintype "passive"))
    )
    (net (code "102") (name "Net-(R4-Pad1)") (class "Default")
      (node (ref "R4") (pin "1") (pinfunction "1_1") (pintype "passive"))
      (node (ref "U7") (pin "2") (pinfunction "2_2") (pintype "passive"))
    )
    (net (code "103") (name "Net-(R5-Pad1)") (class "Default")
      (node (ref "R5") (pin "1") (pinfunction "1_1") (pintype "passive"))
      (node (ref "U12") (pin "2") (pinfunction "2_2") (pintype "passive"))
    )
    (net (code "104") (name "Net-(R6-Pad1)") (class "Default")
      (node (ref "R6") (pin "1") (pinfunction "1_1") (pintype "passive"))
      (node (ref "U11") (pin "2") (pinfunction "2_2") (pintype "passive"))
    )
    (net (code "105") (name "Net-(R7-Pad1)") (class "Default")
      (node (ref "R7") (pin "1") (pinfunction "1_1") (pintype "passive"))
      (node (ref "U9") (pin "2") (pinfunction "2_2") (pintype "passive"))
    )
    (net (code "106") (name "Net-(R8-Pad1)") (class "Default")
      (node (ref "R8") (pin "1") (pinfunction "1_1") (pintype "passive"))
      (node (ref "U10") (pin "2") (pinfunction "2_2") (pintype "passive"))
    )
    (net (code "107") (name "Net-(R9-Pad1)") (class "Default")
      (node (ref "R9") (pin "1") (pinfunction "1_1") (pintype "passive"))
      (node (ref "U20") (pin "2") (pinfunction "2_2") (pintype "passive"))
    )
    (net (code "108") (name "Net-(R10-Pad1)") (class "Default")
      (node (ref "R10") (pin "1") (pinfunction "1_1") (pintype "passive"))
      (node (ref "U19") (pin "2") (pinfunction "2_2") (pintype "passive"))
    )
    (net (code "109") (name "Net-(R11-Pad1)") (class "Default")
      (node (ref "R11") (pin "1") (pinfunction "1_1") (pintype "passive"))
      (node (ref "U17") (pin "2") (pinfunction "2_2") (pintype "passive"))
    )
    (net (code "110") (name "Net-(R12-Pad1)") (class "Default")
      (node (ref "R12") (pin "1") (pinfunction "1_1") (pintype "passive"))
      (node (ref "U18") (pin "2") (pinfunction "2_2") (pintype "passive"))
    )
    (net (code "111") (name "Net-(R13-Pad1)") (class "Default")
      (node (ref "R13") (pin "1") (pinfunction "1_1") (pintype "passive"))
      (node (ref "U13") (pin "2") (pinfunction "2_2") (pintype "passive"))
    )
    (net (code "112") (name "Net-(R14-Pad1)") (class "Default")
      (node (ref "R14") (pin "1") (pinfunction "1_1") (pintype "passive"))
      (node (ref "U14") (pin "2") (pinfunction "2_2") (pintype "passive"))
    )
    (net (code "113") (name "Net-(R15-Pad1)") (class "Default")
      (node (ref "R15") (pin "1") (pinfunction "1_1") (pintype "passive"))
      (node (ref "U16") (pin "2") (pinfunction "2_2") (pintype "passive"))
    )
    (net (code "114") (name "Net-(R16-Pad1)") (class "Default")
      (node (ref "R16") (pin "1") (pinfunction "1_1") (pintype "passive"))
      (node (ref "U15") (pin "2") (pinfunction "2_2") (pintype "passive"))
    )
    (net (code "115") (name "Net-(U1-CSI)") (class "Default")
      (node (ref "R42") (pin "2") (pinfunction "2_2") (pintype "passive"))
      (node (ref "U1") (pin "2") (pinfunction "CSI_2") (pintype "passive"))
    )
    (net (code "116") (name "Net-(U1-VDD)") (class "Default")
      (node (ref "C14") (pin "2") (pinfunction "2_2") (pintype "passive"))
      (node (ref "R36") (pin "1") (pinfunction "1_1") (pintype "passive"))
      (node (ref "U1") (pin "5") (pinfunction "VDD_5") (pintype "passive"))
    )
    (net (code "117") (name "Net-(U2-FB)") (class "Default")
      (node (ref "R46") (pin "1") (pinfunction "1_1") (pintype "passive"))
      (node (ref "R48") (pin "2") (pinfunction "2_2") (pintype "passive"))
      (node (ref "U2") (pin "4") (pinfunction "FB_4") (pintype "passive"))
    )
    (net (code "118") (name "unconnected-(D3-NC-Pad6)") (class "Default")
      (node (ref "D3") (pin "6") (pinfunction "NC_6") (pintype "passive"))
    )
    (net (code "119") (name "unconnected-(D5-VOUT-Pad2)") (class "Default")
      (node (ref "D5") (pin "2") (pinfunction "VOUT_2") (pintype "passive"))
    )
    (net (code "120") (name "unconnected-(D6-Q'H-Pad9)") (class "Default")
      (node (ref "D6") (pin "9") (pinfunction "Q'H_9") (pintype "passive"))
    )
    (net (code "121") (name "unconnected-(D8-NC-Pad6)") (class "Default")
      (node (ref "D8") (pin "6") (pinfunction "NC_6") (pintype "passive"))
    )
    (net (code "122") (name "unconnected-(M3-CLK-Pad20)") (class "Default")
      (node (ref "M3") (pin "20") (pinfunction "CLK_20") (pintype "passive"))
    )
    (net (code "123") (name "unconnected-(M3-CMD-Pad19)") (class "Default")
      (node (ref "M3") (pin "19") (pinfunction "CMD_19") (pintype "passive"))
    )
    (net (code "124") (name "unconnected-(M3-EP-Pad39)") (class "Default")
      (node (ref "M3") (pin "39") (pinfunction "EP_39") (pintype "passive"))
    )
    (net (code "125") (name "unconnected-(M3-IO0-Pad25)") (class "Default")
      (node (ref "M3") (pin "25") (pinfunction "IO0_25") (pintype "passive"))
    )
    (net (code "126") (name "unconnected-(M3-IO12-Pad14)") (class "Default")
      (node (ref "M3") (pin "14") (pinfunction "IO12_14") (pintype "passive"))
    )
    (net (code "127") (name "unconnected-(M3-IO13-Pad16)") (class "Default")
      (node (ref "M3") (pin "16") (pinfunction "IO13_16") (pintype "passive"))
    )
    (net (code "128") (name "unconnected-(M3-IO17-Pad28)") (class "Default")
      (node (ref "M3") (pin "28") (pinfunction "IO17_28") (pintype "passive"))
    )
    (net (code "129") (name "unconnected-(M3-IO21-Pad33)") (class "Default")
      (node (ref "M3") (pin "33") (pinfunction "IO21_33") (pintype "passive"))
    )
    (net (code "130") (name "unconnected-(M3-NC-Pad32)") (class "Default")
      (node (ref "M3") (pin "32") (pinfunction "NC_32") (pintype "passive"))
    )
    (net (code "131") (name "unconnected-(M3-SD0-Pad21)") (class "Default")
      (node (ref "M3") (pin "21") (pinfunction "SD0_21") (pintype "passive"))
    )
    (net (code "132") (name "unconnected-(M3-SD1-Pad22)") (class "Default")
      (node (ref "M3") (pin "22") (pinfunction "SD1_22") (pintype "passive"))
    )
    (net (code "133") (name "unconnected-(M3-SD2-Pad17)") (class "Default")
      (node (ref "M3") (pin "17") (pinfunction "SD2_17") (pintype "passive"))
    )
    (net (code "134") (name "unconnected-(M3-SD3-Pad18)") (class "Default")
      (node (ref "M3") (pin "18") (pinfunction "SD3_18") (pintype "passive"))
    )
    (net (code "135") (name "unconnected-(M3-SENSOR_VN-Pad5)") (class "Default")
      (node (ref "M3") (pin "5") (pinfunction "SENSOR_VN_5") (pintype "passive"))
    )
    (net (code "136") (name "unconnected-(M3-SENSOR_VP-Pad4)") (class "Default")
      (node (ref "M3") (pin "4") (pinfunction "SENSOR_VP_4") (pintype "passive"))
    )
    (net (code "137") (name "unconnected-(M4-PadANT)") (class "Default")
      (node (ref "M4") (pin "ANT") (pinfunction "ANT_ANT") (pintype "passive"))
    )
    (net (code "138") (name "unconnected-(Q2-D12-Pad1)") (class "Default")
      (node (ref "Q2") (pin "1") (pinfunction "D12_1") (pintype "passive"))
    )
    (net (code "139") (name "unconnected-(Q2-D12-Pad8)") (class "Default")
      (node (ref "Q2") (pin "8") (pinfunction "D12_8") (pintype "passive"))
    )
    (net (code "140") (name "unconnected-(SW2-Pad3)") (class "Default")
      (node (ref "SW2") (pin "3") (pinfunction "3_3") (pintype "passive"))
    )
    (net (code "141") (name "unconnected-(SW2-Pad4)") (class "Default")
      (node (ref "SW2") (pin "4") (pinfunction "4_4") (pintype "passive"))
    )
    (net (code "142") (name "unconnected-(SW2-Pad5)") (class "Default")
      (node (ref "SW2") (pin "5") (pinfunction "5_5") (pintype "passive"))
    )
    (net (code "143") (name "unconnected-(SW3-Pad3)") (class "Default")
      (node (ref "SW3") (pin "3") (pinfunction "3_3") (pintype "passive"))
    )
    (net (code "144") (name "unconnected-(SW3-Pad4)") (class "Default")
      (node (ref "SW3") (pin "4") (pinfunction "4_4") (pintype "passive"))
    )
    (net (code "145") (name "unconnected-(SW3-Pad5)") (class "Default")
      (node (ref "SW3") (pin "5") (pinfunction "5_5") (pintype "passive"))
    )
    (net (code "146") (name "unconnected-(U1-TD-Pad4)") (class "Default")
      (node (ref "U1") (pin "4") (pinfunction "TD_4") (pintype "passive"))
    )
    (net (code "147") (name "unconnected-(U2-TAB-Pad6)") (class "Default")
      (node (ref "U2") (pin "6") (pinfunction "TAB_6") (pintype "passive"))
    )
  )
)
